# Nedic.net
KiCad netlist of a schematic drawn in Altium Designer
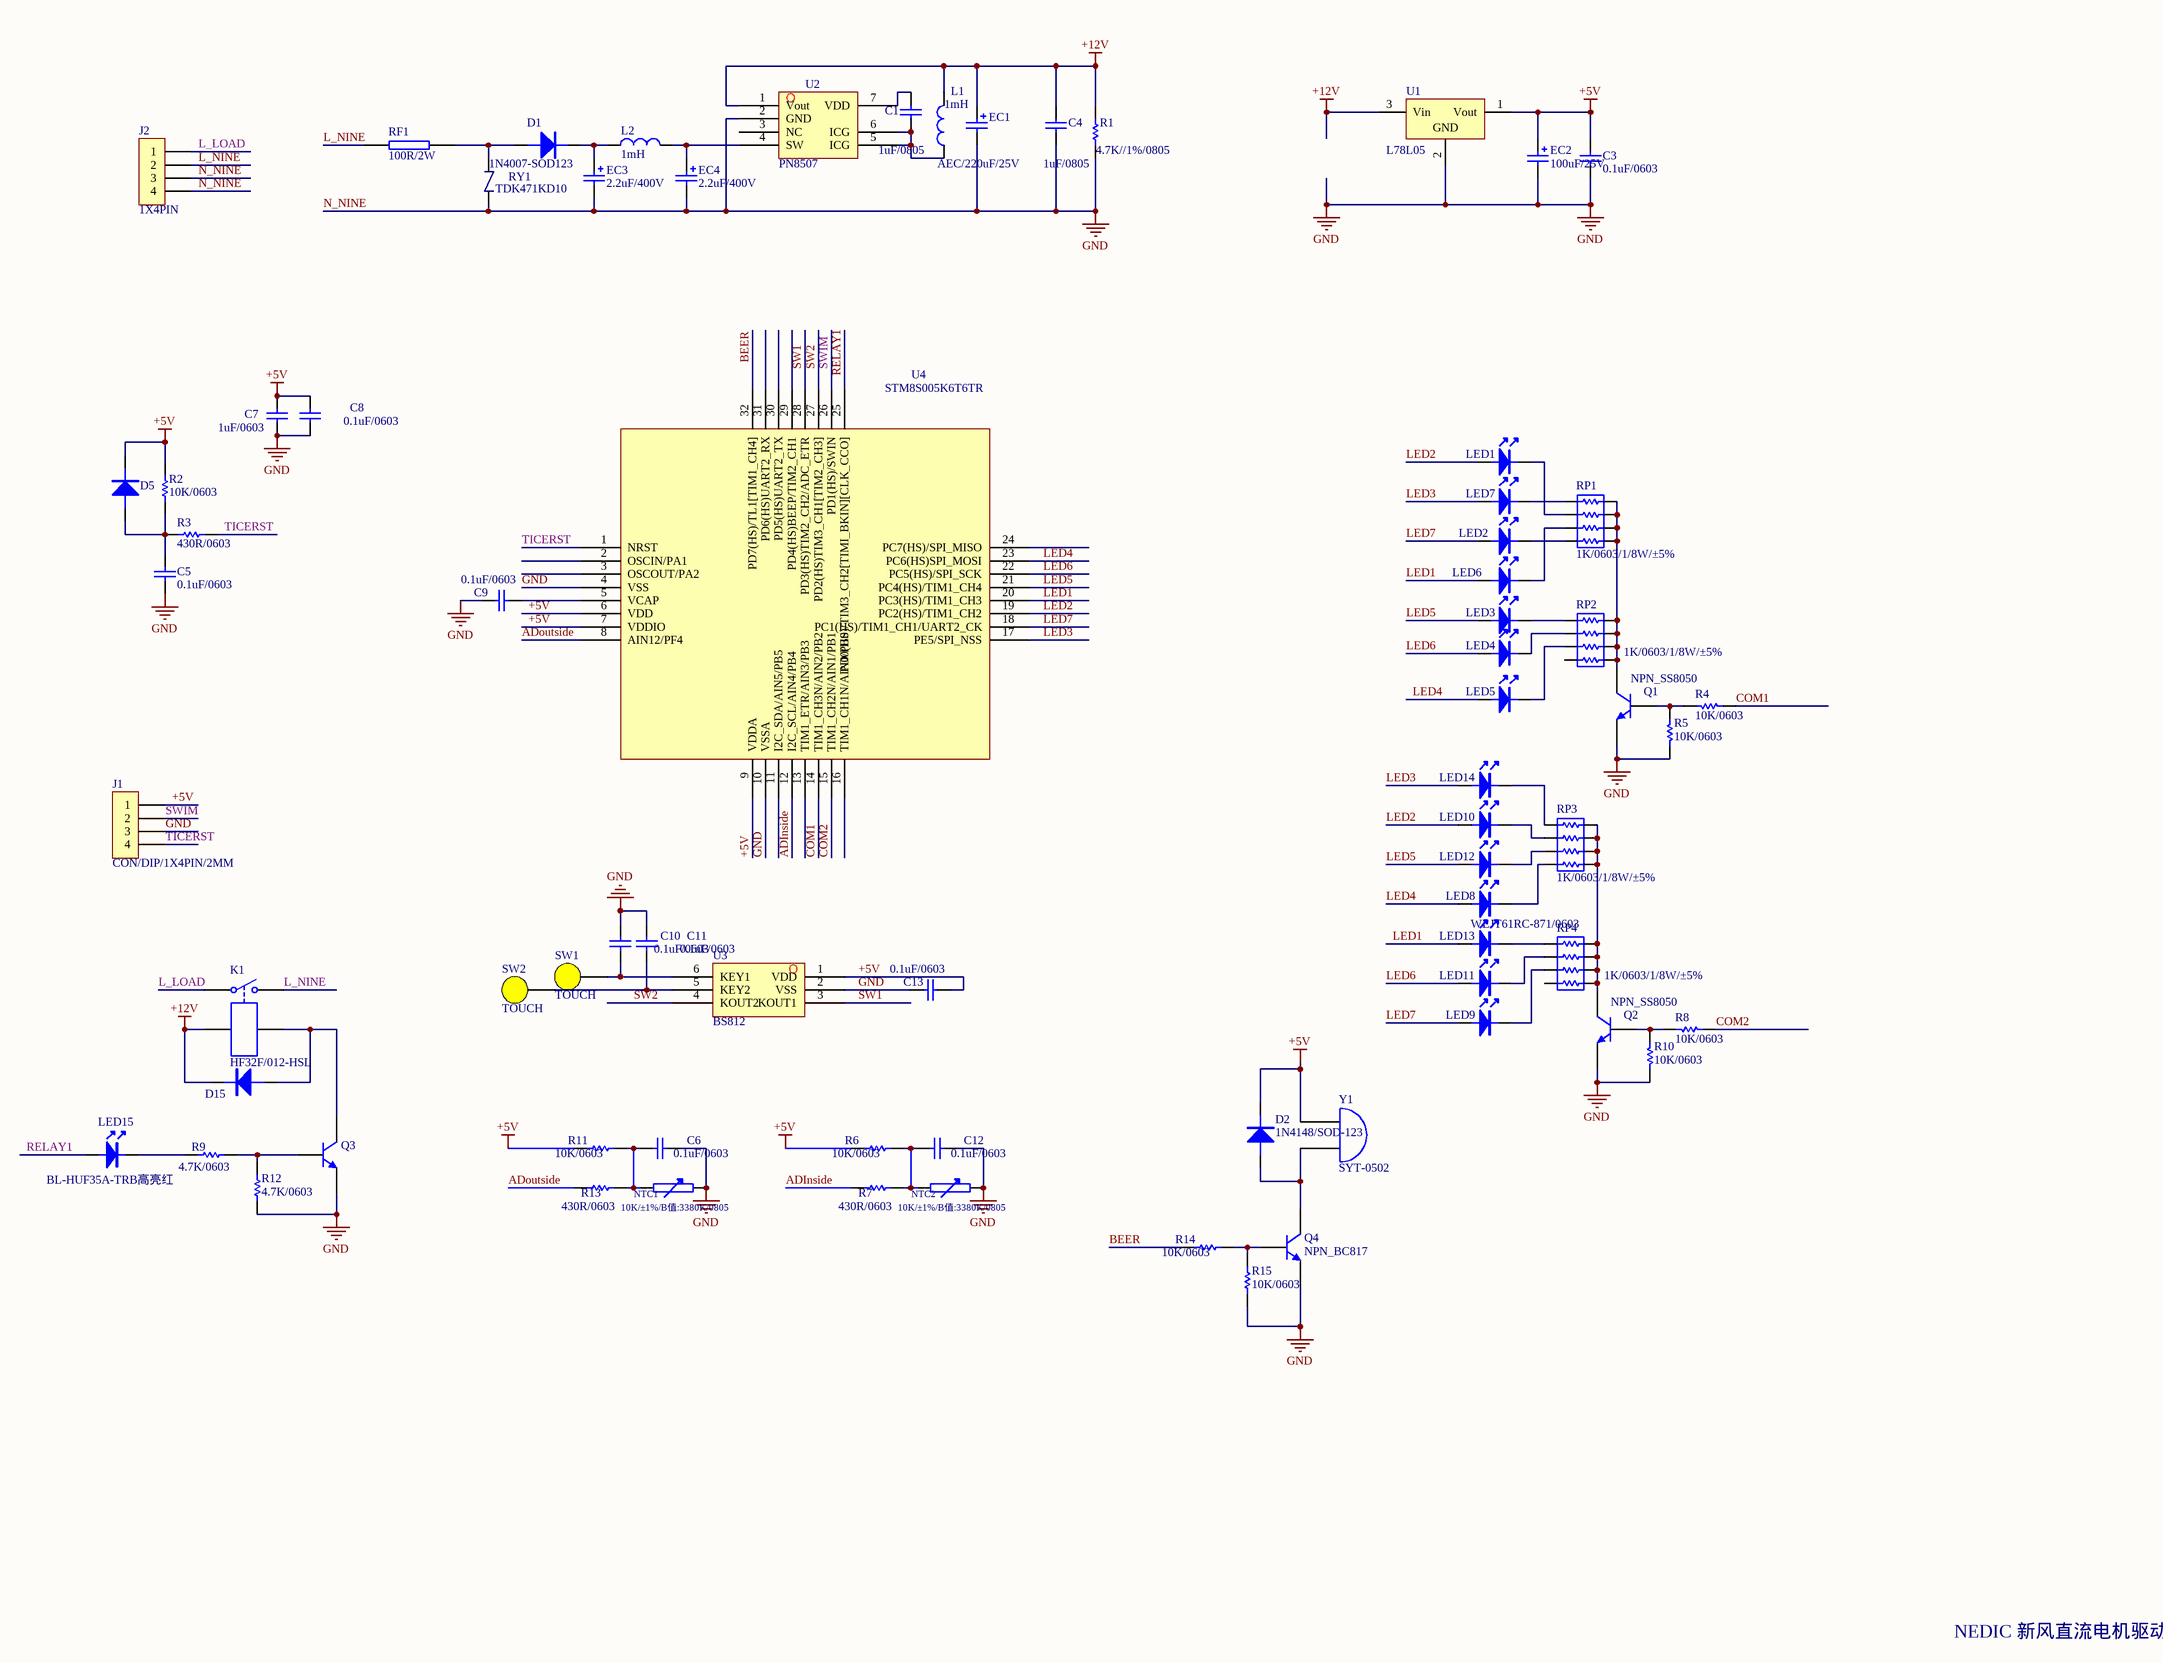
[diagram p0: 新风驱动板Nedic.SchDoc]

(export (version "E")
  (design (tool "Eeschema 10.0.6"))
  (components
    (comp (ref "C1")
      (value "1uF/0805")
      (footprint "CAP/SMT/0805C")
      (libsource (lib "Menred_原理图 封装库") (part "CAP/CAP/SMT/0805C"))
    )
    (comp (ref "C3")
      (value "0.1uF/0603")
      (footprint "CAP/SMT/0603C")
      (libsource (lib "Menred_原理图 封装库") (part "CAP/CAP/SMT/0603C"))
    )
    (comp (ref "C4")
      (value "1uF/0805")
      (footprint "CAP/SMT/0805C")
      (libsource (lib "Menred_原理图 封装库") (part "CAP/CAP/SMT/0805C"))
    )
    (comp (ref "C5")
      (value "0.1uF/0603")
      (footprint "CAP/SMT/0603C")
      (libsource (lib "Menred_原理图 封装库") (part "CAP/CAP/SMT/0603C"))
    )
    (comp (ref "C6")
      (value "0.1uF/0603")
      (footprint "CAP/SMT/0603C")
      (libsource (lib "Menred_原理图 封装库") (part "CAP/CAP/SMT/0603C"))
    )
    (comp (ref "C7")
      (value "1uF/0603")
      (footprint "CAP/SMT/0603C")
      (libsource (lib "Menred_原理图 封装库") (part "CAP/CAP/SMT/0603C"))
    )
    (comp (ref "C8")
      (value "0.1uF/0603")
      (footprint "CAP/SMT/0603C")
      (libsource (lib "Menred_原理图 封装库") (part "CAP/CAP/SMT/0603C"))
    )
    (comp (ref "C9")
      (value "0.1uF/0603")
      (footprint "CAP/SMT/0603C")
      (libsource (lib "Menred_原理图 封装库") (part "CAP/CAP/SMT/0603C"))
    )
    (comp (ref "C10")
      (value "0.1uF/0603")
      (footprint "CAP/SMT/0603C")
      (libsource (lib "Menred_原理图 封装库") (part "CAP/CAP/SMT/0603C"))
    )
    (comp (ref "C11")
      (value "0.1uF/0603")
      (footprint "CAP/SMT/0603C")
      (libsource (lib "Menred_原理图 封装库") (part "CAP/CAP/SMT/0603C"))
    )
    (comp (ref "C12")
      (value "0.1uF/0603")
      (footprint "CAP/SMT/0603C")
      (libsource (lib "Menred_原理图 封装库") (part "CAP/CAP/SMT/0603C"))
    )
    (comp (ref "C13")
      (value "0.1uF/0603")
      (footprint "CAP/SMT/0603C")
      (libsource (lib "Menred_原理图 封装库") (part "CAP/CAP/SMT/0603C"))
    )
    (comp (ref "D1")
      (value "1N4007-SOD123")
      (footprint "D/SMT/SOD123")
      (libsource (lib "二极管类器件") (part "D/D/SMT/1N4007-SOD123"))
    )
    (comp (ref "D2")
      (value "1N4148/SOD-123")
      (footprint "D/SMT/SOD-123")
      (description "VR=75V T(-65-175)P(0.5W)VF=0.6V")
      (libsource (lib "Menred_原理图 封装库") (part "D/D/SMT/1N4148/SOD-123"))
    )
    (comp (ref "D5")
      (value "1N4148/SOD-123")
      (footprint "D/SMT/SOD-123")
      (description "VR=75V T(-65-175)P(0.5W)VF=0.6V")
      (libsource (lib "Menred_原理图 封装库") (part "D/D/SMT/1N4148/SOD-123"))
    )
    (comp (ref "D15")
      (value "1N4148/SOD-123")
      (footprint "D/SMT/SOD-123")
      (description "VR=75V T(-65-175)P(0.5W)VF=0.6V")
      (libsource (lib "Menred_原理图 封装库") (part "D/D/SMT/1N4148/SOD-123"))
    )
    (comp (ref "EC1")
      (value "AEC/220uF/25V")
      (footprint "CAP/DIP/330UF/25V")
      (libsource (lib "Menred_原理图 封装库") (part "CAP/AEC/DIP/330uF/25V"))
    )
    (comp (ref "EC2")
      (value "100uF/25V")
      (footprint "CAP/DIP/100uF/25V")
      (libsource (lib "Menred_原理图 封装库") (part "CAP/AEC/DIP/100uF/25V"))
    )
    (comp (ref "EC3")
      (value "2.2uF/400V")
      (footprint "CAP/DIP/2.2UF/400V/2.5mm")
      (libsource (lib "Menred_原理图 封装库") (part "CAP/AEC/DIP/2.2uF/400V"))
    )
    (comp (ref "EC4")
      (value "2.2uF/400V")
      (footprint "CAP/DIP/2.2UF/400V/2.5mm")
      (libsource (lib "Menred_原理图 封装库") (part "CAP/AEC/DIP/2.2uF/400V"))
    )
    (comp (ref "J1")
      (value "CON/DIP/1X4PIN/2MM")
      (footprint "CON/DIP/1×4PIN/2.0MM")
      (description "Connector")
      (libsource (lib "Menred_原理图 封装库") (part "CON/DIP/1X4PIN/2MM"))
    )
    (comp (ref "J2")
      (value "1X4PIN")
      (footprint "CON/DIP/1×4PIN/5.08MM")
      (description "Connector")
      (libsource (lib "Menred_原理图 封装库") (part "CON/DIP/1X4PIN/5.08MM"))
    )
    (comp (ref "K1")
      (value "HF32F/012-HSL")
      (footprint "RELAY/HF32F-012-HSL")
      (libsource (lib "Menred_原理图 封装库") (part "RELAY/GENERAL/DIP/HF32F/012-HSL"))
    )
    (comp (ref "L1")
      (value "1mH")
      (footprint "L/DIP/1mH")
      (description "工字电感")
      (libsource (lib "Menred_原理图 封装库") (part "L/L/DIP/JYGX68-1.0mH/300mA"))
    )
    (comp (ref "L2")
      (value "1mH")
      (footprint "L/DIP/1mH")
      (description "工字电感")
      (libsource (lib "Menred_原理图 封装库") (part "L/L/DIP/JYGX68-1.0mH/300mA"))
    )
    (comp (ref "LED1")
      (value "WEJT61RC-871/0603")
      (footprint "D/SMT/LED/0603")
      (libsource (lib "Menred_原理图 封装库") (part "D/LED/SMT/WEJT61RC-871/0603"))
    )
    (comp (ref "LED2")
      (value "WEJT61RC-871/0603")
      (footprint "D/SMT/LED/0603")
      (libsource (lib "Menred_原理图 封装库") (part "D/LED/SMT/WEJT61RC-871/0603"))
    )
    (comp (ref "LED3")
      (value "WEJT61RC-871/0603")
      (footprint "D/SMT/LED/0603")
      (libsource (lib "Menred_原理图 封装库") (part "D/LED/SMT/WEJT61RC-871/0603"))
    )
    (comp (ref "LED4")
      (value "WEJT61RC-871/0603")
      (footprint "D/SMT/LED/0603")
      (libsource (lib "Menred_原理图 封装库") (part "D/LED/SMT/WEJT61RC-871/0603"))
    )
    (comp (ref "LED5")
      (value "WEJT61RC-871/0603")
      (footprint "D/SMT/LED/0603")
      (libsource (lib "Menred_原理图 封装库") (part "D/LED/SMT/WEJT61RC-871/0603"))
    )
    (comp (ref "LED6")
      (value "WEJT61RC-871/0603")
      (footprint "D/SMT/LED/0603")
      (libsource (lib "Menred_原理图 封装库") (part "D/LED/SMT/WEJT61RC-871/0603"))
    )
    (comp (ref "LED7")
      (value "WEJT61RC-871/0603")
      (footprint "D/SMT/LED/0603")
      (libsource (lib "Menred_原理图 封装库") (part "D/LED/SMT/WEJT61RC-871/0603"))
    )
    (comp (ref "LED8")
      (value "WEJT61RC-871/0603")
      (footprint "D/SMT/LED/0603")
      (libsource (lib "Menred_原理图 封装库") (part "D/LED/SMT/WEJT61RC-871/0603"))
    )
    (comp (ref "LED9")
      (value "WEJT61RC-871/0603")
      (footprint "D/SMT/LED/0603")
      (libsource (lib "Menred_原理图 封装库") (part "D/LED/SMT/WEJT61RC-871/0603"))
    )
    (comp (ref "LED10")
      (value "WEJT61RC-871/0603")
      (footprint "D/SMT/LED/0603")
      (libsource (lib "Menred_原理图 封装库") (part "D/LED/SMT/WEJT61RC-871/0603"))
    )
    (comp (ref "LED11")
      (value "WEJT61RC-871/0603")
      (footprint "D/SMT/LED/0603")
      (libsource (lib "Menred_原理图 封装库") (part "D/LED/SMT/WEJT61RC-871/0603"))
    )
    (comp (ref "LED12")
      (value "WEJT61RC-871/0603")
      (footprint "D/SMT/LED/0603")
      (libsource (lib "Menred_原理图 封装库") (part "D/LED/SMT/WEJT61RC-871/0603"))
    )
    (comp (ref "LED13")
      (value "WEJT61RC-871/0603")
      (footprint "D/SMT/LED/0603")
      (libsource (lib "Menred_原理图 封装库") (part "D/LED/SMT/WEJT61RC-871/0603"))
    )
    (comp (ref "LED14")
      (value "WEJT61RC-871/0603")
      (footprint "D/SMT/LED/0603")
      (libsource (lib "Menred_原理图 封装库") (part "D/LED/SMT/WEJT61RC-871/0603"))
    )
    (comp (ref "LED15")
      (value "BL-HUF35A-TRB高亮红")
      (footprint "D/SMT/LED/0805")
      (libsource (lib "Menred_原理图 封装库") (part "D/LED/SMT/BL-HUF35A-TRB高亮红/0805"))
    )
    (comp (ref "NTC1")
      (value "10K/±1%/B值:3380K/0805")
      (footprint "Sensor/S_NTC_DIP")
      (description "3380(10K)")
      (libsource (lib "Menred_原理图 封装库") (part "SENSOR/NTC_SMD"))
    )
    (comp (ref "NTC2")
      (value "10K/±1%/B值:3380K/0805")
      (footprint "CON/DIP/1×2PIN/2.54MM/插件端子")
      (description "3380(10K)")
      (libsource (lib "Menred_原理图 封装库") (part "SENSOR/NTC_SMD"))
    )
    (comp (ref "Q1")
      (value "NPN_SS8050")
      (footprint "BJT/SMT/SOT-23")
      (description "Vce25V/Vcb40V/Veb5V/Ic1.5V/Pd300mW")
      (fields (field (name "PUBLISHER") "*"))
      (libsource (lib "Menred_原理图 封装库") (part "BJT/NPN/SMT/SS8050/SOT-23"))
    )
    (comp (ref "Q2")
      (value "NPN_SS8050")
      (footprint "BJT/SMT/SOT-23")
      (description "Vce25V/Vcb40V/Veb5V/Ic1.5V/Pd300mW")
      (fields (field (name "PUBLISHER") "*"))
      (libsource (lib "Menred_原理图 封装库") (part "BJT/NPN/SMT/SS8050/SOT-23"))
    )
    (comp (ref "Q3")
      (value "NPN_SS8050")
      (footprint "BJT/SMT/SOT-23")
      (fields (field (name "PUBLISHER") "*"))
      (libsource (lib "Menred_原理图 封装库") (part "BJT/NPN/SMT/SS8050/SOT-23"))
    )
    (comp (ref "Q4")
      (value "NPN_BC817")
      (footprint "BJT/SMT/SOT-23")
      (fields (field (name "PUBLISHER") "*"))
      (libsource (lib "Menred_原理图 封装库") (part "BJT/NPN/SMT/BC817/SOT-23"))
    )
    (comp (ref "R1")
      (value "4.7K//1%/0805")
      (footprint "0805R")
      (libsource (lib "Menred_原理图 封装库") (part "RES/RES/SMT/0805"))
    )
    (comp (ref "R2")
      (value "10K/0603")
      (footprint "0603R")
      (libsource (lib "Menred_原理图 封装库") (part "RES/RES/SMT/0603"))
    )
    (comp (ref "R3")
      (value "430R/0603")
      (footprint "0603R")
      (libsource (lib "Menred_原理图 封装库") (part "RES/RES/SMT/0603"))
    )
    (comp (ref "R4")
      (value "10K/0603")
      (footprint "0603R")
      (libsource (lib "Menred_原理图 封装库") (part "RES/RES/SMT/0603"))
    )
    (comp (ref "R5")
      (value "10K/0603")
      (footprint "0603R")
      (libsource (lib "Menred_原理图 封装库") (part "RES/RES/SMT/0603"))
    )
    (comp (ref "R6")
      (value "10K/0603")
      (footprint "0603R")
      (libsource (lib "Menred_原理图 封装库") (part "RES/RES/SMT/0603"))
    )
    (comp (ref "R7")
      (value "430R/0603")
      (footprint "0603R")
      (libsource (lib "Menred_原理图 封装库") (part "RES/RES/SMT/0603"))
    )
    (comp (ref "R8")
      (value "10K/0603")
      (footprint "0603R")
      (libsource (lib "Menred_原理图 封装库") (part "RES/RES/SMT/0603"))
    )
    (comp (ref "R9")
      (value "4.7K/0603")
      (footprint "0603R")
      (libsource (lib "Menred_原理图 封装库") (part "RES/RES/SMT/0603"))
    )
    (comp (ref "R10")
      (value "10K/0603")
      (footprint "0603R")
      (libsource (lib "Menred_原理图 封装库") (part "RES/RES/SMT/0603"))
    )
    (comp (ref "R11")
      (value "10K/0603")
      (footprint "0603R")
      (libsource (lib "Menred_原理图 封装库") (part "RES/RES/SMT/0603"))
    )
    (comp (ref "R12")
      (value "4.7K/0603")
      (footprint "0603R")
      (libsource (lib "Menred_原理图 封装库") (part "RES/RES/SMT/0603"))
    )
    (comp (ref "R13")
      (value "430R/0603")
      (footprint "0603R")
      (libsource (lib "Menred_原理图 封装库") (part "RES/RES/SMT/0603"))
    )
    (comp (ref "R14")
      (value "10K/0603")
      (footprint "0603R")
      (libsource (lib "Menred_原理图 封装库") (part "RES/RES/SMT/0603"))
    )
    (comp (ref "R15")
      (value "10K/0603")
      (footprint "0603R")
      (libsource (lib "Menred_原理图 封装库") (part "RES/RES/SMT/0603"))
    )
    (comp (ref "RF1")
      (value "100R/2W")
      (footprint "FUSE/3.15A")
      (libsource (lib "Menred_原理图 封装库") (part "FUSE/FUSE/DIP/3.15A"))
    )
    (comp (ref "RP1")
      (value "1K/0603/1/8W/±5%")
      (footprint "0603R*4")
      (description "Isolated Resistor Network")
      (fields (field (name "PUBLISHER") "Altium Limited"))
      (libsource (lib "Menred_原理图 封装库") (part "RES /PACKS/SMT/0603*4"))
    )
    (comp (ref "RP2")
      (value "1K/0603/1/8W/±5%")
      (footprint "0603R*4")
      (description "Isolated Resistor Network")
      (fields (field (name "PUBLISHER") "Altium Limited"))
      (libsource (lib "Menred_原理图 封装库") (part "RES /PACKS/SMT/0603*4"))
    )
    (comp (ref "RP3")
      (value "1K/0603/1/8W/±5%")
      (footprint "0603R*4")
      (description "Isolated Resistor Network")
      (fields (field (name "PUBLISHER") "Altium Limited"))
      (libsource (lib "Menred_原理图 封装库") (part "RES /PACKS/SMT/0603*4"))
    )
    (comp (ref "RP4")
      (value "1K/0603/1/8W/±5%")
      (footprint "0603R*4")
      (description "Isolated Resistor Network")
      (fields (field (name "PUBLISHER") "Altium Limited"))
      (libsource (lib "Menred_原理图 封装库") (part "RES /PACKS/SMT/0603*4"))
    )
    (comp (ref "RY1")
      (value "TDK471KD10")
      (footprint "RES/RY/TDK471KD10")
      (libsource (lib "Menred_原理图 封装库") (part "RES/RY/DIP/TDK471KD10"))
    )
    (comp (ref "SW1")
      (value "TOUCH")
      (footprint "SWITCH/TOUCH-2")
      (libsource (lib "Menred_原理图 封装库") (part "SWITCH/TOUCH"))
    )
    (comp (ref "SW2")
      (value "TOUCH")
      (footprint "SWITCH/TOUCH-2")
      (libsource (lib "Menred_原理图 封装库") (part "SWITCH/TOUCH"))
    )
    (comp (ref "U1")
      (value "L78L05")
      (footprint "SOT-89-3L(78L05)")
      (description "5V三端稳压器 output imax 0.1A")
      (fields (field (name "MANUFACTURER") "Generic Components"))
      (libsource (lib "Menred_原理图 封装库") (part "IC/POWER/SMT/L78L05/SOT-89"))
    )
    (comp (ref "U2")
      (value "PN8507")
      (footprint "SOP-7")
      (libsource (lib "集成芯片类") (part "IC/POWER/SMT/PN8507/SOP-8"))
    )
    (comp (ref "U3")
      (value "BS812")
      (footprint "SOT23-6")
      (libsource (lib "Menred_原理图 封装库") (part "IC/POWER/SMT/BS812"))
    )
    (comp (ref "U4")
      (value "STM8S005K6T6TR")
      (footprint "LQFP32")
      (libsource (lib "Menred_原理图 封装库") (part "MCU/SMT/STM8S005K6T6TR/LQFP32"))
    )
    (comp (ref "Y1")
      (value "SYT-0502")
      (footprint "SYT-5020")
      (libsource (lib "Menred_原理图 封装库") (part "OTHER/BEER/SYT-0502"))
    )
  )
  (nets
    (net (code "1") (name "+5V") (class "Default")
      (node (ref "C13") (pin "1") (pinfunction "1_1") (pintype "passive"))
      (node (ref "C3") (pin "2") (pinfunction "2_2") (pintype "passive"))
      (node (ref "C7") (pin "2") (pinfunction "2_2") (pintype "passive"))
      (node (ref "C8") (pin "2") (pinfunction "2_2") (pintype "passive"))
      (node (ref "D2") (pin "1") (pinfunction "K_1") (pintype "passive"))
      (node (ref "D5") (pin "1") (pinfunction "K_1") (pintype "passive"))
      (node (ref "EC2") (pin "1") (pinfunction "1_1") (pintype "passive"))
      (node (ref "J1") (pin "1") (pinfunction "1_1") (pintype "passive"))
      (node (ref "R11") (pin "2") (pinfunction "2_2") (pintype "passive"))
      (node (ref "R2") (pin "1") (pinfunction "1_1") (pintype "passive"))
      (node (ref "R6") (pin "2") (pinfunction "2_2") (pintype "passive"))
      (node (ref "U1") (pin "1") (pinfunction "Vout_1") (pintype "passive"))
      (node (ref "U3") (pin "1") (pinfunction "VDD_1") (pintype "passive"))
      (node (ref "U4") (pin "6") (pinfunction "VDD_6") (pintype "power_in"))
      (node (ref "U4") (pin "7") (pinfunction "VDDIO_7") (pintype "power_in"))
      (node (ref "U4") (pin "9") (pinfunction "VDDA_9") (pintype "power_in"))
      (node (ref "Y1") (pin "1") (pinfunction "1_1") (pintype "passive"))
    )
    (net (code "2") (name "+12V") (class "Default")
      (node (ref "C4") (pin "2") (pinfunction "2_2") (pintype "passive"))
      (node (ref "D15") (pin "1") (pinfunction "K_1") (pintype "passive"))
      (node (ref "EC1") (pin "1") (pinfunction "1_1") (pintype "passive"))
      (node (ref "K1") (pin "3") (pinfunction "3_3") (pintype "passive"))
      (node (ref "L1") (pin "2") (pinfunction "2_2") (pintype "passive"))
      (node (ref "R1") (pin "2") (pinfunction "2_2") (pintype "passive"))
      (node (ref "U1") (pin "3") (pinfunction "Vin_3") (pintype "passive"))
      (node (ref "U2") (pin "1") (pinfunction "Vout_1") (pintype "passive"))
    )
    (net (code "3") (name "/ADInside") (class "Default")
      (node (ref "R7") (pin "2") (pinfunction "2_2") (pintype "passive"))
      (node (ref "U4") (pin "12") (pinfunction "I2C_SCL/AIN4/PB4_12") (pintype "power_in"))
    )
    (net (code "4") (name "/ADoutside") (class "Default")
      (node (ref "R13") (pin "2") (pinfunction "2_2") (pintype "passive"))
      (node (ref "U4") (pin "8") (pinfunction "AIN12/PF4_8") (pintype "power_in"))
    )
    (net (code "5") (name "/BEER") (class "Default")
      (node (ref "R14") (pin "2") (pinfunction "2_2") (pintype "passive"))
      (node (ref "U4") (pin "32") (pinfunction "PD7(HS)/TL1[TIM1_CH4]_32") (pintype "power_in"))
    )
    (net (code "6") (name "/COM1") (class "Default")
      (node (ref "R4") (pin "1") (pinfunction "1_1") (pintype "passive"))
      (node (ref "U4") (pin "14") (pinfunction "TIM1_CH3N/AIN2/PB2_14") (pintype "power_in"))
    )
    (net (code "7") (name "/COM2") (class "Default")
      (node (ref "R8") (pin "1") (pinfunction "1_1") (pintype "passive"))
      (node (ref "U4") (pin "15") (pinfunction "TIM1_CH2N/AIN1/PB1_15") (pintype "power_in"))
    )
    (net (code "8") (name "/LED1") (class "Default")
      (node (ref "LED13") (pin "2") (pinfunction "A_2") (pintype "passive"))
      (node (ref "LED6") (pin "2") (pinfunction "A_2") (pintype "passive"))
      (node (ref "U4") (pin "20") (pinfunction "PC3(HS)/TIM1_CH3_20") (pintype "power_in"))
    )
    (net (code "9") (name "/LED2") (class "Default")
      (node (ref "LED1") (pin "2") (pinfunction "A_2") (pintype "passive"))
      (node (ref "LED10") (pin "2") (pinfunction "A_2") (pintype "passive"))
      (node (ref "U4") (pin "19") (pinfunction "PC2(HS)/TIM1_CH2_19") (pintype "power_in"))
    )
    (net (code "10") (name "/LED3") (class "Default")
      (node (ref "LED14") (pin "2") (pinfunction "A_2") (pintype "passive"))
      (node (ref "LED7") (pin "2") (pinfunction "A_2") (pintype "passive"))
      (node (ref "U4") (pin "17") (pinfunction "PE5/SPI_NSS_17") (pintype "power_in"))
    )
    (net (code "11") (name "/LED4") (class "Default")
      (node (ref "LED5") (pin "2") (pinfunction "A_2") (pintype "passive"))
      (node (ref "LED8") (pin "2") (pinfunction "A_2") (pintype "passive"))
      (node (ref "U4") (pin "23") (pinfunction "PC6(HS)SPI_MOSI_23") (pintype "power_in"))
    )
    (net (code "12") (name "/LED5") (class "Default")
      (node (ref "LED12") (pin "2") (pinfunction "A_2") (pintype "passive"))
      (node (ref "LED3") (pin "2") (pinfunction "A_2") (pintype "passive"))
      (node (ref "U4") (pin "21") (pinfunction "PC4(HS)/TIM1_CH4_21") (pintype "power_in"))
    )
    (net (code "13") (name "/LED6") (class "Default")
      (node (ref "LED11") (pin "2") (pinfunction "A_2") (pintype "passive"))
      (node (ref "LED4") (pin "2") (pinfunction "A_2") (pintype "passive"))
      (node (ref "U4") (pin "22") (pinfunction "PC5(HS)/SPI_SCK_22") (pintype "power_in"))
    )
    (net (code "14") (name "/LED7") (class "Default")
      (node (ref "LED2") (pin "2") (pinfunction "A_2") (pintype "passive"))
      (node (ref "LED9") (pin "2") (pinfunction "A_2") (pintype "passive"))
      (node (ref "U4") (pin "18") (pinfunction "PC1(HS)/TIM1_CH1/UART2_CK_18") (pintype "power_in"))
    )
    (net (code "15") (name "/L_LOAD") (class "Default")
      (node (ref "J2") (pin "1") (pinfunction "1_1") (pintype "passive"))
      (node (ref "K1") (pin "1") (pinfunction "1_1") (pintype "passive"))
    )
    (net (code "16") (name "/L_NINE") (class "Default")
      (node (ref "J2") (pin "2") (pinfunction "2_2") (pintype "passive"))
      (node (ref "K1") (pin "2") (pinfunction "2_2") (pintype "passive"))
      (node (ref "RF1") (pin "2") (pinfunction "2_2") (pintype "passive"))
    )
    (net (code "17") (name "/RELAY1") (class "Default")
      (node (ref "LED15") (pin "2") (pinfunction "A_2") (pintype "passive"))
      (node (ref "U4") (pin "25") (pinfunction "PD0(HS)/TIM3_CH2[TIMI_BKIN][CLK_CCO]_25") (pintype "power_in"))
    )
    (net (code "18") (name "/SW1") (class "Default")
      (node (ref "U3") (pin "3") (pinfunction "KOUT1_3") (pintype "passive"))
      (node (ref "U4") (pin "28") (pinfunction "PD3(HS)TIM2_CH2/ADC_ETR_28") (pintype "power_in"))
    )
    (net (code "19") (name "/SW2") (class "Default")
      (node (ref "U3") (pin "4") (pinfunction "KOUT2_4") (pintype "passive"))
      (node (ref "U4") (pin "27") (pinfunction "PD2(HS)TIM3_CH1[TIM2_CH3]_27") (pintype "power_in"))
    )
    (net (code "20") (name "/SWIM") (class "Default")
      (node (ref "J1") (pin "2") (pinfunction "2_2") (pintype "passive"))
      (node (ref "U4") (pin "26") (pinfunction "PD1(HS)/SWIN_26") (pintype "power_in"))
    )
    (net (code "21") (name "/TICERST") (class "Default")
      (node (ref "J1") (pin "4") (pinfunction "4_4") (pintype "passive"))
      (node (ref "R3") (pin "2") (pinfunction "2_2") (pintype "passive"))
      (node (ref "U4") (pin "1") (pinfunction "NRST_1") (pintype "power_in"))
    )
    (net (code "22") (name "GND") (class "Default")
      (node (ref "C10") (pin "2") (pinfunction "2_2") (pintype "passive"))
      (node (ref "C11") (pin "2") (pinfunction "2_2") (pintype "passive"))
      (node (ref "C12") (pin "1") (pinfunction "1_1") (pintype "passive"))
      (node (ref "C13") (pin "2") (pinfunction "2_2") (pintype "passive"))
      (node (ref "C3") (pin "1") (pinfunction "1_1") (pintype "passive"))
      (node (ref "C4") (pin "1") (pinfunction "1_1") (pintype "passive"))
      (node (ref "C5") (pin "2") (pinfunction "2_2") (pintype "passive"))
      (node (ref "C6") (pin "1") (pinfunction "1_1") (pintype "passive"))
      (node (ref "C7") (pin "1") (pinfunction "1_1") (pintype "passive"))
      (node (ref "C8") (pin "1") (pinfunction "1_1") (pintype "passive"))
      (node (ref "C9") (pin "2") (pinfunction "2_2") (pintype "passive"))
      (node (ref "EC1") (pin "2") (pinfunction "2_2") (pintype "passive"))
      (node (ref "EC2") (pin "2") (pinfunction "2_2") (pintype "passive"))
      (node (ref "EC3") (pin "2") (pinfunction "2_2") (pintype "passive"))
      (node (ref "EC4") (pin "2") (pinfunction "2_2") (pintype "passive"))
      (node (ref "J1") (pin "3") (pinfunction "3_3") (pintype "passive"))
      (node (ref "J2") (pin "3") (pinfunction "3_3") (pintype "passive"))
      (node (ref "J2") (pin "4") (pinfunction "4_4") (pintype "passive"))
      (node (ref "NTC1") (pin "2") (pinfunction "2_2") (pintype "passive"))
      (node (ref "NTC2") (pin "2") (pinfunction "2_2") (pintype "passive"))
      (node (ref "Q1") (pin "2") (pinfunction "E_2") (pintype "passive"))
      (node (ref "Q2") (pin "2") (pinfunction "E_2") (pintype "passive"))
      (node (ref "Q3") (pin "2") (pinfunction "E_2") (pintype "passive"))
      (node (ref "Q4") (pin "2") (pinfunction "E_2") (pintype "passive"))
      (node (ref "R1") (pin "1") (pinfunction "1_1") (pintype "passive"))
      (node (ref "R10") (pin "2") (pinfunction "2_2") (pintype "passive"))
      (node (ref "R12") (pin "2") (pinfunction "2_2") (pintype "passive"))
      (node (ref "R15") (pin "2") (pinfunction "2_2") (pintype "passive"))
      (node (ref "R5") (pin "2") (pinfunction "2_2") (pintype "passive"))
      (node (ref "RY1") (pin "1") (pinfunction "1_1") (pintype "passive"))
      (node (ref "U1") (pin "2") (pinfunction "GND_2") (pintype "passive"))
      (node (ref "U2") (pin "2") (pinfunction "GND_2") (pintype "passive"))
      (node (ref "U3") (pin "2") (pinfunction "VSS_2") (pintype "passive"))
      (node (ref "U4") (pin "10") (pinfunction "VSSA_10") (pintype "power_in"))
      (node (ref "U4") (pin "4") (pinfunction "VSS_4") (pintype "power_in"))
    )
    (net (code "23") (name "Net-(C1-Pad1)") (class "Default")
      (node (ref "C1") (pin "1") (pinfunction "1_1") (pintype "passive"))
      (node (ref "L1") (pin "1") (pinfunction "1_1") (pintype "passive"))
      (node (ref "U2") (pin "5") (pinfunction "ICG_5") (pintype "passive"))
      (node (ref "U2") (pin "6") (pinfunction "ICG_6") (pintype "passive"))
    )
    (net (code "24") (name "Net-(C6-Pad2)") (class "Default")
      (node (ref "C6") (pin "2") (pinfunction "2_2") (pintype "passive"))
      (node (ref "NTC1") (pin "1") (pinfunction "1_1") (pintype "passive"))
      (node (ref "R11") (pin "1") (pinfunction "1_1") (pintype "passive"))
      (node (ref "R13") (pin "1") (pinfunction "1_1") (pintype "passive"))
    )
    (net (code "25") (name "Net-(C12-Pad2)") (class "Default")
      (node (ref "C12") (pin "2") (pinfunction "2_2") (pintype "passive"))
      (node (ref "NTC2") (pin "1") (pinfunction "1_1") (pintype "passive"))
      (node (ref "R6") (pin "1") (pinfunction "1_1") (pintype "passive"))
      (node (ref "R7") (pin "1") (pinfunction "1_1") (pintype "passive"))
    )
    (net (code "26") (name "Net-(D1-A)") (class "Default")
      (node (ref "D1") (pin "2") (pinfunction "A_2") (pintype "passive"))
      (node (ref "RF1") (pin "1") (pinfunction "1_1") (pintype "passive"))
      (node (ref "RY1") (pin "2") (pinfunction "2_2") (pintype "passive"))
    )
    (net (code "27") (name "Net-(D1-K)") (class "Default")
      (node (ref "D1") (pin "1") (pinfunction "K_1") (pintype "passive"))
      (node (ref "EC3") (pin "1") (pinfunction "1_1") (pintype "passive"))
      (node (ref "L2") (pin "1") (pinfunction "1_1") (pintype "passive"))
    )
    (net (code "28") (name "Net-(D2-A)") (class "Default")
      (node (ref "D2") (pin "2") (pinfunction "A_2") (pintype "passive"))
      (node (ref "Q4") (pin "3") (pinfunction "C_3") (pintype "passive"))
      (node (ref "Y1") (pin "2") (pinfunction "2_2") (pintype "passive"))
    )
    (net (code "29") (name "Net-(D5-A)") (class "Default")
      (node (ref "C5") (pin "1") (pinfunction "1_1") (pintype "passive"))
      (node (ref "D5") (pin "2") (pinfunction "A_2") (pintype "passive"))
      (node (ref "R2") (pin "2") (pinfunction "2_2") (pintype "passive"))
      (node (ref "R3") (pin "1") (pinfunction "1_1") (pintype "passive"))
    )
    (net (code "30") (name "Net-(D15-A)") (class "Default")
      (node (ref "D15") (pin "2") (pinfunction "A_2") (pintype "passive"))
      (node (ref "K1") (pin "4") (pinfunction "4_4") (pintype "passive"))
      (node (ref "Q3") (pin "3") (pinfunction "C_3") (pintype "passive"))
    )
    (net (code "31") (name "Net-(LED1-K)") (class "Default")
      (node (ref "LED1") (pin "1") (pinfunction "K_1") (pintype "passive"))
      (node (ref "RP1") (pin "6") (pinfunction "6_6") (pintype "passive"))
    )
    (net (code "32") (name "Net-(LED2-K)") (class "Default")
      (node (ref "LED2") (pin "1") (pinfunction "K_1") (pintype "passive"))
      (node (ref "RP1") (pin "8") (pinfunction "8_8") (pintype "passive"))
    )
    (net (code "33") (name "Net-(LED3-K)") (class "Default")
      (node (ref "LED3") (pin "1") (pinfunction "K_1") (pintype "passive"))
      (node (ref "RP2") (pin "5") (pinfunction "5_5") (pintype "passive"))
    )
    (net (code "34") (name "Net-(LED4-K)") (class "Default")
      (node (ref "LED4") (pin "1") (pinfunction "K_1") (pintype "passive"))
      (node (ref "RP2") (pin "6") (pinfunction "6_6") (pintype "passive"))
    )
    (net (code "35") (name "Net-(LED5-K)") (class "Default")
      (node (ref "LED5") (pin "1") (pinfunction "K_1") (pintype "passive"))
      (node (ref "RP2") (pin "7") (pinfunction "7_7") (pintype "passive"))
    )
    (net (code "36") (name "Net-(LED6-K)") (class "Default")
      (node (ref "LED6") (pin "1") (pinfunction "K_1") (pintype "passive"))
      (node (ref "RP1") (pin "7") (pinfunction "7_7") (pintype "passive"))
    )
    (net (code "37") (name "Net-(LED7-K)") (class "Default")
      (node (ref "LED7") (pin "1") (pinfunction "K_1") (pintype "passive"))
      (node (ref "RP1") (pin "5") (pinfunction "5_5") (pintype "passive"))
    )
    (net (code "38") (name "Net-(LED8-K)") (class "Default")
      (node (ref "LED8") (pin "1") (pinfunction "K_1") (pintype "passive"))
      (node (ref "RP3") (pin "8") (pinfunction "8_8") (pintype "passive"))
    )
    (net (code "39") (name "Net-(LED9-K)") (class "Default")
      (node (ref "LED9") (pin "1") (pinfunction "K_1") (pintype "passive"))
      (node (ref "RP4") (pin "7") (pinfunction "7_7") (pintype "passive"))
    )
    (net (code "40") (name "Net-(LED10-K)") (class "Default")
      (node (ref "LED10") (pin "1") (pinfunction "K_1") (pintype "passive"))
      (node (ref "RP3") (pin "6") (pinfunction "6_6") (pintype "passive"))
    )
    (net (code "41") (name "Net-(LED11-K)") (class "Default")
      (node (ref "LED11") (pin "1") (pinfunction "K_1") (pintype "passive"))
      (node (ref "RP4") (pin "6") (pinfunction "6_6") (pintype "passive"))
    )
    (net (code "42") (name "Net-(LED12-K)") (class "Default")
      (node (ref "LED12") (pin "1") (pinfunction "K_1") (pintype "passive"))
      (node (ref "RP3") (pin "7") (pinfunction "7_7") (pintype "passive"))
    )
    (net (code "43") (name "Net-(LED13-K)") (class "Default")
      (node (ref "LED13") (pin "1") (pinfunction "K_1") (pintype "passive"))
      (node (ref "RP4") (pin "5") (pinfunction "5_5") (pintype "passive"))
    )
    (net (code "44") (name "Net-(LED14-K)") (class "Default")
      (node (ref "LED14") (pin "1") (pinfunction "K_1") (pintype "passive"))
      (node (ref "RP3") (pin "5") (pinfunction "5_5") (pintype "passive"))
    )
    (net (code "45") (name "Net-(LED15-K)") (class "Default")
      (node (ref "LED15") (pin "1") (pinfunction "K_1") (pintype "passive"))
      (node (ref "R9") (pin "2") (pinfunction "2_2") (pintype "passive"))
    )
    (net (code "46") (name "Net-(Q1-B)") (class "Default")
      (node (ref "Q1") (pin "1") (pinfunction "B_1") (pintype "passive"))
      (node (ref "R4") (pin "2") (pinfunction "2_2") (pintype "passive"))
      (node (ref "R5") (pin "1") (pinfunction "1_1") (pintype "passive"))
    )
    (net (code "47") (name "Net-(Q1-C)") (class "Default")
      (node (ref "Q1") (pin "3") (pinfunction "C_3") (pintype "passive"))
      (node (ref "RP1") (pin "1") (pinfunction "1_1") (pintype "passive"))
      (node (ref "RP1") (pin "2") (pinfunction "2_2") (pintype "passive"))
      (node (ref "RP1") (pin "3") (pinfunction "3_3") (pintype "passive"))
      (node (ref "RP1") (pin "4") (pinfunction "4_4") (pintype "passive"))
      (node (ref "RP2") (pin "1") (pinfunction "1_1") (pintype "passive"))
      (node (ref "RP2") (pin "2") (pinfunction "2_2") (pintype "passive"))
      (node (ref "RP2") (pin "3") (pinfunction "3_3") (pintype "passive"))
      (node (ref "RP2") (pin "4") (pinfunction "4_4") (pintype "passive"))
    )
    (net (code "48") (name "Net-(Q2-B)") (class "Default")
      (node (ref "Q2") (pin "1") (pinfunction "B_1") (pintype "passive"))
      (node (ref "R10") (pin "1") (pinfunction "1_1") (pintype "passive"))
      (node (ref "R8") (pin "2") (pinfunction "2_2") (pintype "passive"))
    )
    (net (code "49") (name "Net-(Q2-C)") (class "Default")
      (node (ref "Q2") (pin "3") (pinfunction "C_3") (pintype "passive"))
      (node (ref "RP3") (pin "1") (pinfunction "1_1") (pintype "passive"))
      (node (ref "RP3") (pin "2") (pinfunction "2_2") (pintype "passive"))
      (node (ref "RP3") (pin "3") (pinfunction "3_3") (pintype "passive"))
      (node (ref "RP3") (pin "4") (pinfunction "4_4") (pintype "passive"))
      (node (ref "RP4") (pin "1") (pinfunction "1_1") (pintype "passive"))
      (node (ref "RP4") (pin "2") (pinfunction "2_2") (pintype "passive"))
      (node (ref "RP4") (pin "3") (pinfunction "3_3") (pintype "passive"))
      (node (ref "RP4") (pin "4") (pinfunction "4_4") (pintype "passive"))
    )
    (net (code "50") (name "Net-(Q3-B)") (class "Default")
      (node (ref "Q3") (pin "1") (pinfunction "B_1") (pintype "passive"))
      (node (ref "R12") (pin "1") (pinfunction "1_1") (pintype "passive"))
      (node (ref "R9") (pin "1") (pinfunction "1_1") (pintype "passive"))
    )
    (net (code "51") (name "Net-(Q4-B)") (class "Default")
      (node (ref "Q4") (pin "1") (pinfunction "B_1") (pintype "passive"))
      (node (ref "R14") (pin "1") (pinfunction "1_1") (pintype "passive"))
      (node (ref "R15") (pin "1") (pinfunction "1_1") (pintype "passive"))
    )
    (net (code "52") (name "Net-(U2-SW)") (class "Default")
      (node (ref "EC4") (pin "1") (pinfunction "1_1") (pintype "passive"))
      (node (ref "L2") (pin "2") (pinfunction "2_2") (pintype "passive"))
      (node (ref "U2") (pin "4") (pinfunction "SW_4") (pintype "passive"))
    )
    (net (code "53") (name "Net-(U2-VDD)") (class "Default")
      (node (ref "C1") (pin "2") (pinfunction "2_2") (pintype "passive"))
      (node (ref "U2") (pin "7") (pinfunction "VDD_7") (pintype "passive"))
    )
    (net (code "54") (name "Net-(U3-KEY1)") (class "Default")
      (node (ref "C10") (pin "1") (pinfunction "1_1") (pintype "passive"))
      (node (ref "SW1") (pin "1") (pinfunction "1_1") (pintype "passive"))
      (node (ref "U3") (pin "6") (pinfunction "KEY1_6") (pintype "passive"))
    )
    (net (code "55") (name "Net-(U3-KEY2)") (class "Default")
      (node (ref "C11") (pin "1") (pinfunction "1_1") (pintype "passive"))
      (node (ref "SW2") (pin "1") (pinfunction "1_1") (pintype "passive"))
      (node (ref "U3") (pin "5") (pinfunction "KEY2_5") (pintype "passive"))
    )
    (net (code "56") (name "Net-(U4-VCAP)") (class "Default")
      (node (ref "C9") (pin "1") (pinfunction "1_1") (pintype "passive"))
      (node (ref "U4") (pin "5") (pinfunction "VCAP_5") (pintype "power_in"))
    )
    (net (code "57") (name "unconnected-(RP2-Pad8)") (class "Default")
      (node (ref "RP2") (pin "8") (pinfunction "8_8") (pintype "passive"))
    )
    (net (code "58") (name "unconnected-(RP4-Pad8)") (class "Default")
      (node (ref "RP4") (pin "8") (pinfunction "8_8") (pintype "passive"))
    )
    (net (code "59") (name "unconnected-(U2-NC-Pad3)") (class "Default")
      (node (ref "U2") (pin "3") (pinfunction "NC_3") (pintype "passive"))
    )
    (net (code "60") (name "unconnected-(U4-I2C_SDA{slash}AIN5{slash}PB5-Pad11)") (class "Default")
      (node (ref "U4") (pin "11") (pinfunction "I2C_SDA/AIN5/PB5_11") (pintype "power_in"))
    )
    (net (code "61") (name "unconnected-(U4-OSCIN{slash}PA1-Pad2)") (class "Default")
      (node (ref "U4") (pin "2") (pinfunction "OSCIN/PA1_2") (pintype "power_in"))
    )
    (net (code "62") (name "unconnected-(U4-OSCOUT{slash}PA2-Pad3)") (class "Default")
      (node (ref "U4") (pin "3") (pinfunction "OSCOUT/PA2_3") (pintype "power_in"))
    )
    (net (code "63") (name "unconnected-(U4-PC7(HS){slash}SPI_MISO-Pad24)") (class "Default")
      (node (ref "U4") (pin "24") (pinfunction "PC7(HS)/SPI_MISO_24") (pintype "power_in"))
    )
    (net (code "64") (name "unconnected-(U4-PD4(HS)BEEP{slash}TIM2_CH1-Pad29)") (class "Default")
      (node (ref "U4") (pin "29") (pinfunction "PD4(HS)BEEP/TIM2_CH1_29") (pintype "power_in"))
    )
    (net (code "65") (name "unconnected-(U4-PD5(HS)UART2_TX-Pad30)") (class "Default")
      (node (ref "U4") (pin "30") (pinfunction "PD5(HS)UART2_TX_30") (pintype "power_in"))
    )
    (net (code "66") (name "unconnected-(U4-PD6(HS)UART2_RX-Pad31)") (class "Default")
      (node (ref "U4") (pin "31") (pinfunction "PD6(HS)UART2_RX_31") (pintype "power_in"))
    )
    (net (code "67") (name "unconnected-(U4-TIM1_CH1N{slash}AIN0{slash}PB0-Pad16)") (class "Default")
      (node (ref "U4") (pin "16") (pinfunction "TIM1_CH1N/AIN0/PB0_16") (pintype "power_in"))
    )
    (net (code "68") (name "unconnected-(U4-TIM1_ETR{slash}AIN3{slash}PB3-Pad13)") (class "Default")
      (node (ref "U4") (pin "13") (pinfunction "TIM1_ETR/AIN3/PB3_13") (pintype "power_in"))
    )
    (net (code "69") (name "unconnected-(Y1-Pad3)") (class "Default")
      (node (ref "Y1") (pin "3") (pinfunction "3_3") (pintype "passive"))
    )
  )
)
